# pulse_module.net
KiCad netlist of a schematic drawn in EAGLE
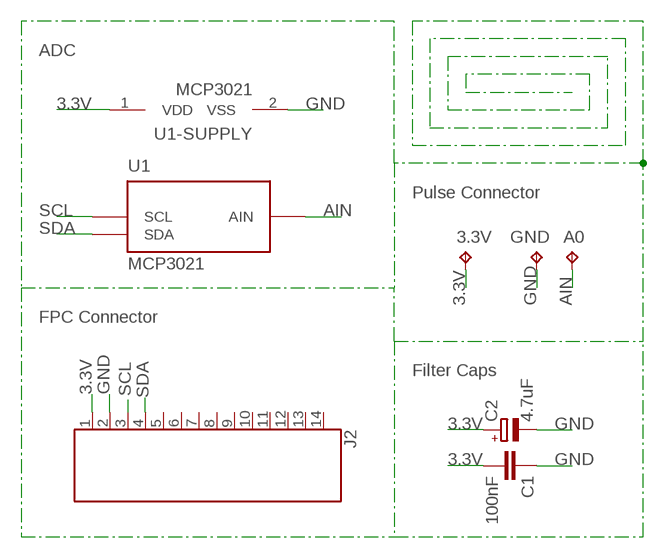
[diagram p0: schematic, sheet 1]

(export (version "E")
  (design (tool "Eeschema 10.0.6"))
  (components
    (comp (ref "3.3V")
      (value "TPTP20R")
      (footprint "eagle-import:TP20R")
      (libsource (lib "eagle-import") (part "TPTP20R"))
    )
    (comp (ref "A0")
      (value "TPTP20R")
      (footprint "eagle-import:TP20R")
      (libsource (lib "eagle-import") (part "TPTP20R"))
    )
    (comp (ref "C1")
      (value "100nF")
      (footprint "eagle-import:C1206")
      (libsource (lib "eagle-import") (part "C-EUC1206"))
    )
    (comp (ref "C2")
      (value "4.7uF")
      (footprint "eagle-import:SMC_A")
      (libsource (lib "eagle-import") (part "CPOL-EUSMCA"))
    )
    (comp (ref "GND")
      (value "TPTP20R")
      (footprint "eagle-import:TP20R")
      (libsource (lib "eagle-import") (part "TPTP20R"))
    )
    (comp (ref "J2")
      (value "686114183522")
      (footprint "eagle-import:686114183522")
      (libsource (lib "eagle-import") (part "686114183522"))
    )
    (comp (ref "U1")
      (value "MCP3021")
      (footprint "eagle-import:SOT-23-5")
      (fields
        (field (name "MANUFACTURER") "Microchip Technology")
        (field (name "PART_NUMBER") "MCP3021A5T-E/OT")
      )
      (libsource (lib "eagle-import") (part "MCP3210"))
    )
  )
  (nets
    (net (code "1") (name "/3.3V") (class "Default")
      (node (ref "3.3V") (pin "TP") (pinfunction "TP_TP") (pintype "input"))
      (node (ref "C1") (pin "2") (pinfunction "2_2") (pintype "passive"))
      (node (ref "C2") (pin "+") (pinfunction "+_+") (pintype "passive"))
      (node (ref "J2") (pin "1") (pinfunction "14_1") (pintype "passive"))
      (node (ref "U1") (pin "1") (pinfunction "VDD_1") (pintype "power_in"))
    )
    (net (code "2") (name "/AIN") (class "Default")
      (node (ref "A0") (pin "TP") (pinfunction "TP_TP") (pintype "input"))
      (node (ref "U1") (pin "3") (pinfunction "AIN_3") (pintype "input"))
    )
    (net (code "3") (name "/GND") (class "Default")
      (node (ref "C1") (pin "1") (pinfunction "1_1") (pintype "passive"))
      (node (ref "C2") (pin "-") (pinfunction "-_-") (pintype "passive"))
      (node (ref "GND") (pin "TP") (pinfunction "TP_TP") (pintype "input"))
      (node (ref "J2") (pin "2") (pinfunction "13_2") (pintype "passive"))
      (node (ref "U1") (pin "2") (pinfunction "VSS_2") (pintype "power_in"))
    )
    (net (code "4") (name "/SCL") (class "Default")
      (node (ref "J2") (pin "3") (pinfunction "12_3") (pintype "passive"))
      (node (ref "U1") (pin "5") (pinfunction "SCL_5") (pintype "bidirectional"))
    )
    (net (code "5") (name "/SDA") (class "Default")
      (node (ref "J2") (pin "4") (pinfunction "11_4") (pintype "passive"))
      (node (ref "U1") (pin "4") (pinfunction "SDA_4") (pintype "bidirectional"))
    )
    (net (code "6") (name "unconnected-(J2-1-Pad14)") (class "Default")
      (node (ref "J2") (pin "14") (pinfunction "1_14") (pintype "passive"))
    )
    (net (code "7") (name "unconnected-(J2-2-Pad13)") (class "Default")
      (node (ref "J2") (pin "13") (pinfunction "2_13") (pintype "passive"))
    )
    (net (code "8") (name "unconnected-(J2-3-Pad12)") (class "Default")
      (node (ref "J2") (pin "12") (pinfunction "3_12") (pintype "passive"))
    )
    (net (code "9") (name "unconnected-(J2-4-Pad11)") (class "Default")
      (node (ref "J2") (pin "11") (pinfunction "4_11") (pintype "passive"))
    )
    (net (code "10") (name "unconnected-(J2-5-Pad10)") (class "Default")
      (node (ref "J2") (pin "10") (pinfunction "5_10") (pintype "passive"))
    )
    (net (code "11") (name "unconnected-(J2-6-Pad9)") (class "Default")
      (node (ref "J2") (pin "9") (pinfunction "6_9") (pintype "passive"))
    )
    (net (code "12") (name "unconnected-(J2-7-Pad8)") (class "Default")
      (node (ref "J2") (pin "8") (pinfunction "7_8") (pintype "passive"))
    )
    (net (code "13") (name "unconnected-(J2-8-Pad7)") (class "Default")
      (node (ref "J2") (pin "7") (pinfunction "8_7") (pintype "passive"))
    )
    (net (code "14") (name "unconnected-(J2-9-Pad6)") (class "Default")
      (node (ref "J2") (pin "6") (pinfunction "9_6") (pintype "passive"))
    )
    (net (code "15") (name "unconnected-(J2-10-Pad5)") (class "Default")
      (node (ref "J2") (pin "5") (pinfunction "10_5") (pintype "passive"))
    )
  )
)
